# HDC1000_breakout.net
KiCad netlist of a schematic drawn in EAGLE
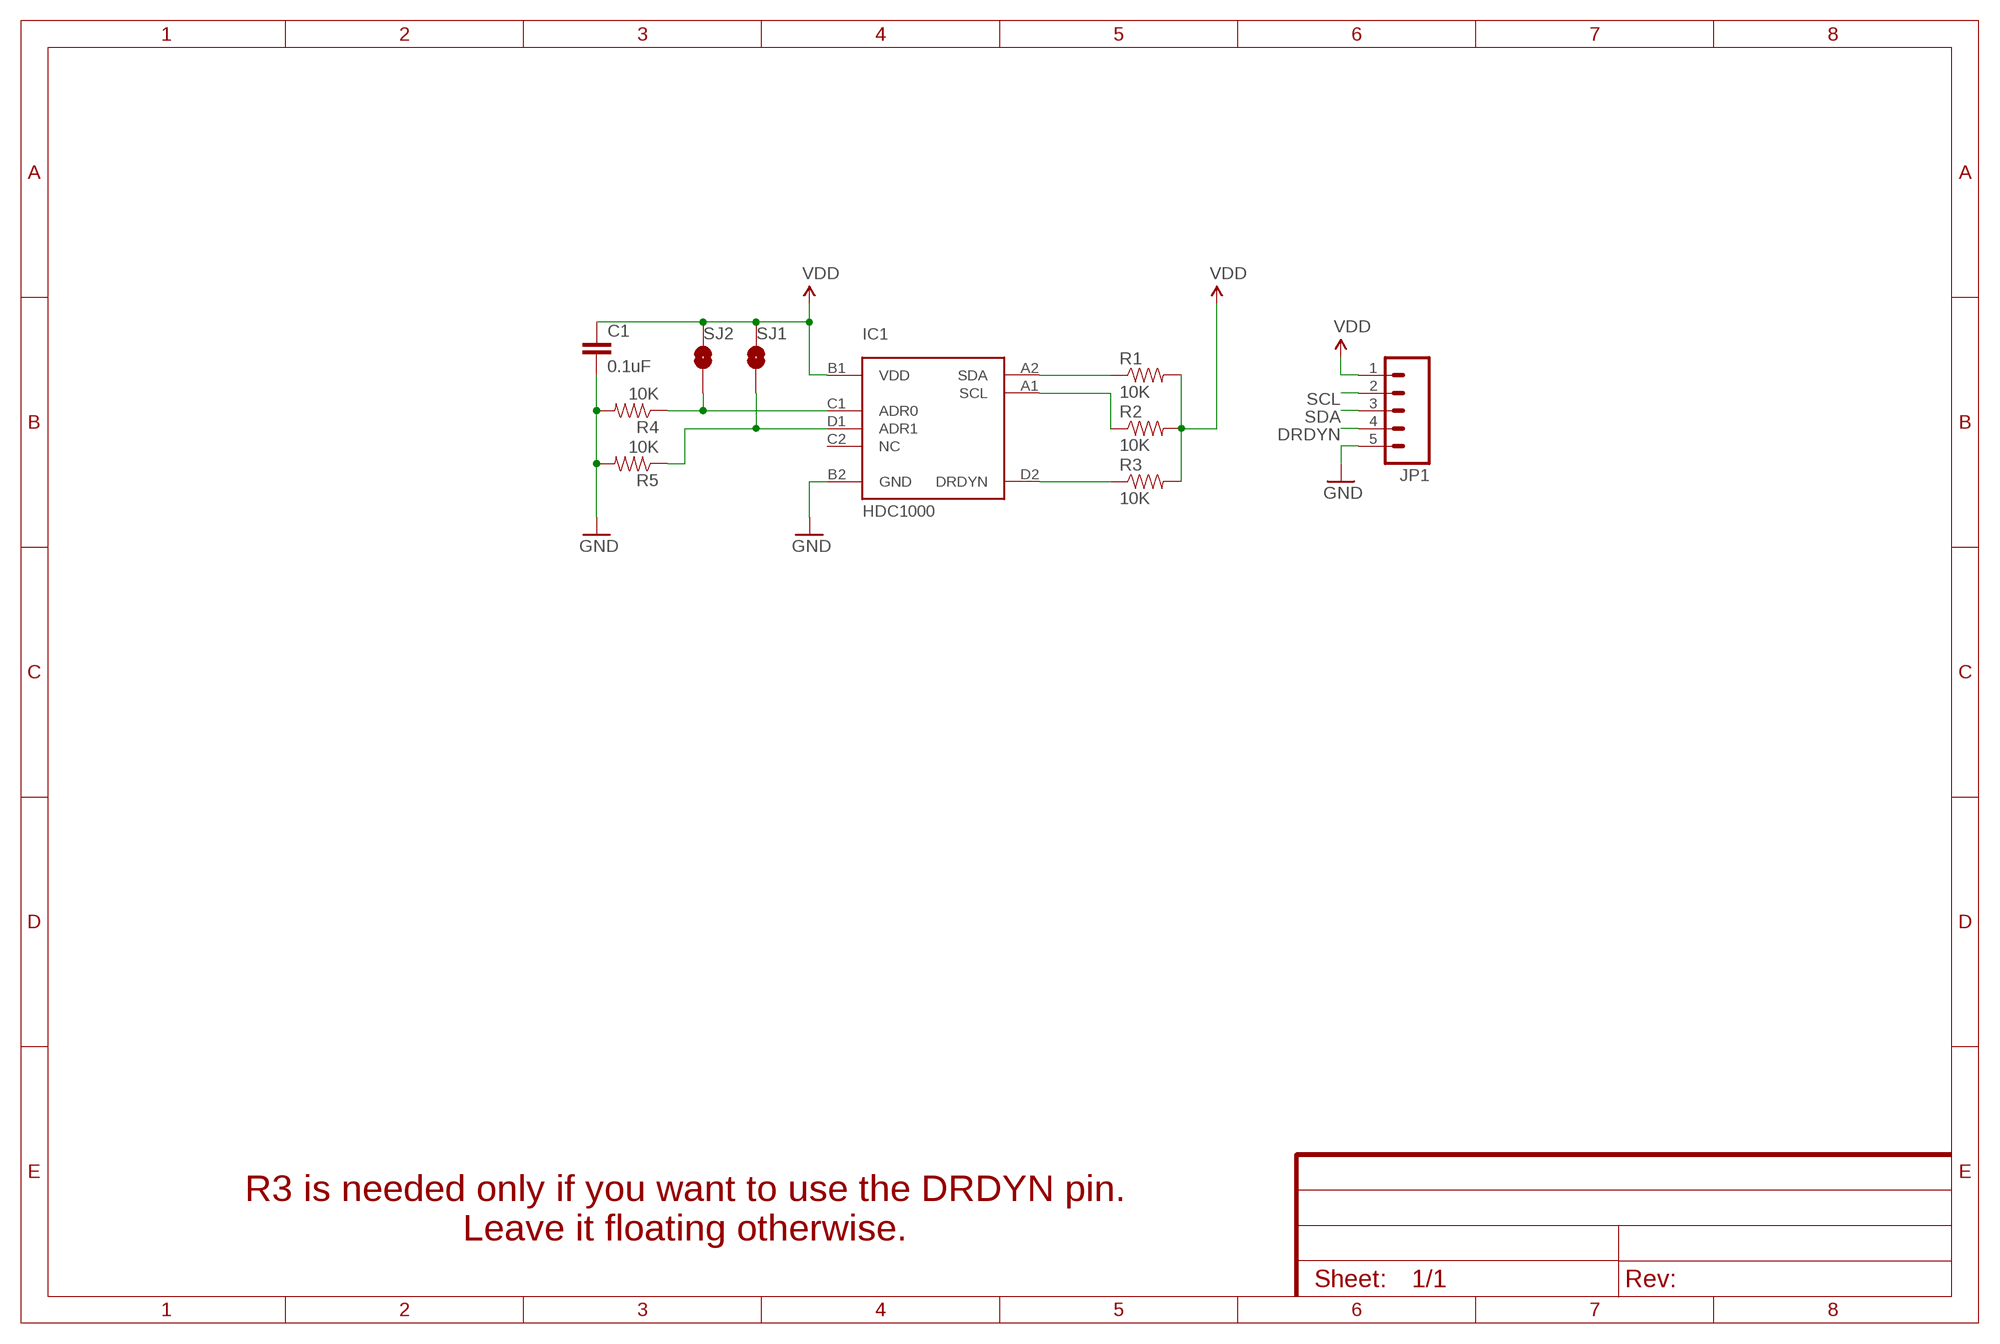
[diagram p0: schematic, sheet 1]

(export (version "E")
  (design (tool "Eeschema 10.0.6"))
  (components
    (comp (ref "C1")
      (value "0.1uF")
      (footprint "eagle-import:0805")
      (libsource (lib "eagle-import") (part "CAP0805"))
    )
    (comp (ref "IC1")
      (value "HDC1000")
      (footprint "eagle-import:DSBGA_8_YPA")
      (libsource (lib "eagle-import") (part "HDC1000"))
    )
    (comp (ref "JP1")
      (value "M05LOCK")
      (footprint "eagle-import:1X05_LOCK")
      (libsource (lib "eagle-import") (part "M05LOCK"))
    )
    (comp (ref "R1")
      (value "10K")
      (footprint "eagle-import:0805")
      (libsource (lib "eagle-import") (part "RESISTOR0805-RES"))
    )
    (comp (ref "R2")
      (value "10K")
      (footprint "eagle-import:0805")
      (libsource (lib "eagle-import") (part "RESISTOR0805-RES"))
    )
    (comp (ref "R3")
      (value "10K")
      (footprint "eagle-import:0805")
      (libsource (lib "eagle-import") (part "RESISTOR0805-RES"))
    )
    (comp (ref "R4")
      (value "10K")
      (footprint "eagle-import:0805")
      (libsource (lib "eagle-import") (part "RESISTOR0805-RES"))
    )
    (comp (ref "R5")
      (value "10K")
      (footprint "eagle-import:0805")
      (libsource (lib "eagle-import") (part "RESISTOR0805-RES"))
    )
    (comp (ref "SJ1")
      (value "SOLDERJUMPERNO")
      (footprint "eagle-import:SJ_2S-NO")
      (libsource (lib "eagle-import") (part "SOLDERJUMPERNO"))
    )
    (comp (ref "SJ2")
      (value "SOLDERJUMPERNO")
      (footprint "eagle-import:SJ_2S-NO")
      (libsource (lib "eagle-import") (part "SOLDERJUMPERNO"))
    )
  )
  (nets
    (net (code "1") (name "/DRDYN") (class "Default")
      (node (ref "IC1") (pin "D2") (pinfunction "DRDYN_D2") (pintype "output"))
      (node (ref "JP1") (pin "4") (pinfunction "4_4") (pintype "passive"))
      (node (ref "R3") (pin "1") (pinfunction "1_1") (pintype "passive"))
    )
    (net (code "2") (name "/SCL") (class "Default")
      (node (ref "IC1") (pin "A1") (pinfunction "SCL_A1") (pintype "input"))
      (node (ref "JP1") (pin "2") (pinfunction "2_2") (pintype "passive"))
      (node (ref "R2") (pin "1") (pinfunction "1_1") (pintype "passive"))
    )
    (net (code "3") (name "/SDA") (class "Default")
      (node (ref "IC1") (pin "A2") (pinfunction "SDA_A2") (pintype "bidirectional"))
      (node (ref "JP1") (pin "3") (pinfunction "3_3") (pintype "passive"))
      (node (ref "R1") (pin "1") (pinfunction "1_1") (pintype "passive"))
    )
    (net (code "4") (name "GND") (class "Default")
      (node (ref "C1") (pin "2") (pinfunction "2_2") (pintype "passive"))
      (node (ref "IC1") (pin "B2") (pinfunction "GND_B2") (pintype "power_in"))
      (node (ref "JP1") (pin "5") (pinfunction "5_5") (pintype "passive"))
      (node (ref "R4") (pin "2") (pinfunction "2_2") (pintype "passive"))
      (node (ref "R5") (pin "2") (pinfunction "2_2") (pintype "passive"))
    )
    (net (code "5") (name "Net-(IC1-ADR0)") (class "Default")
      (node (ref "IC1") (pin "C1") (pinfunction "ADR0_C1") (pintype "input"))
      (node (ref "R4") (pin "1") (pinfunction "1_1") (pintype "passive"))
      (node (ref "SJ2") (pin "2") (pinfunction "2_2") (pintype "passive"))
    )
    (net (code "6") (name "Net-(IC1-ADR1)") (class "Default")
      (node (ref "IC1") (pin "D1") (pinfunction "ADR1_D1") (pintype "input"))
      (node (ref "R5") (pin "1") (pinfunction "1_1") (pintype "passive"))
      (node (ref "SJ1") (pin "2") (pinfunction "2_2") (pintype "passive"))
    )
    (net (code "7") (name "VDD") (class "Default")
      (node (ref "C1") (pin "1") (pinfunction "1_1") (pintype "passive"))
      (node (ref "IC1") (pin "B1") (pinfunction "VDD_B1") (pintype "power_in"))
      (node (ref "JP1") (pin "1") (pinfunction "1_1") (pintype "passive"))
      (node (ref "R1") (pin "2") (pinfunction "2_2") (pintype "passive"))
      (node (ref "R2") (pin "2") (pinfunction "2_2") (pintype "passive"))
      (node (ref "R3") (pin "2") (pinfunction "2_2") (pintype "passive"))
      (node (ref "SJ1") (pin "1") (pinfunction "1_1") (pintype "passive"))
      (node (ref "SJ2") (pin "1") (pinfunction "1_1") (pintype "passive"))
    )
    (net (code "8") (name "unconnected-(IC1-NC-PadC2)") (class "Default")
      (node (ref "IC1") (pin "C2") (pinfunction "NC_C2") (pintype "no_connect"))
    )
  )
)
